# StepperMotorDrivers.net
KiCad netlist of a schematic drawn in Altium Designer
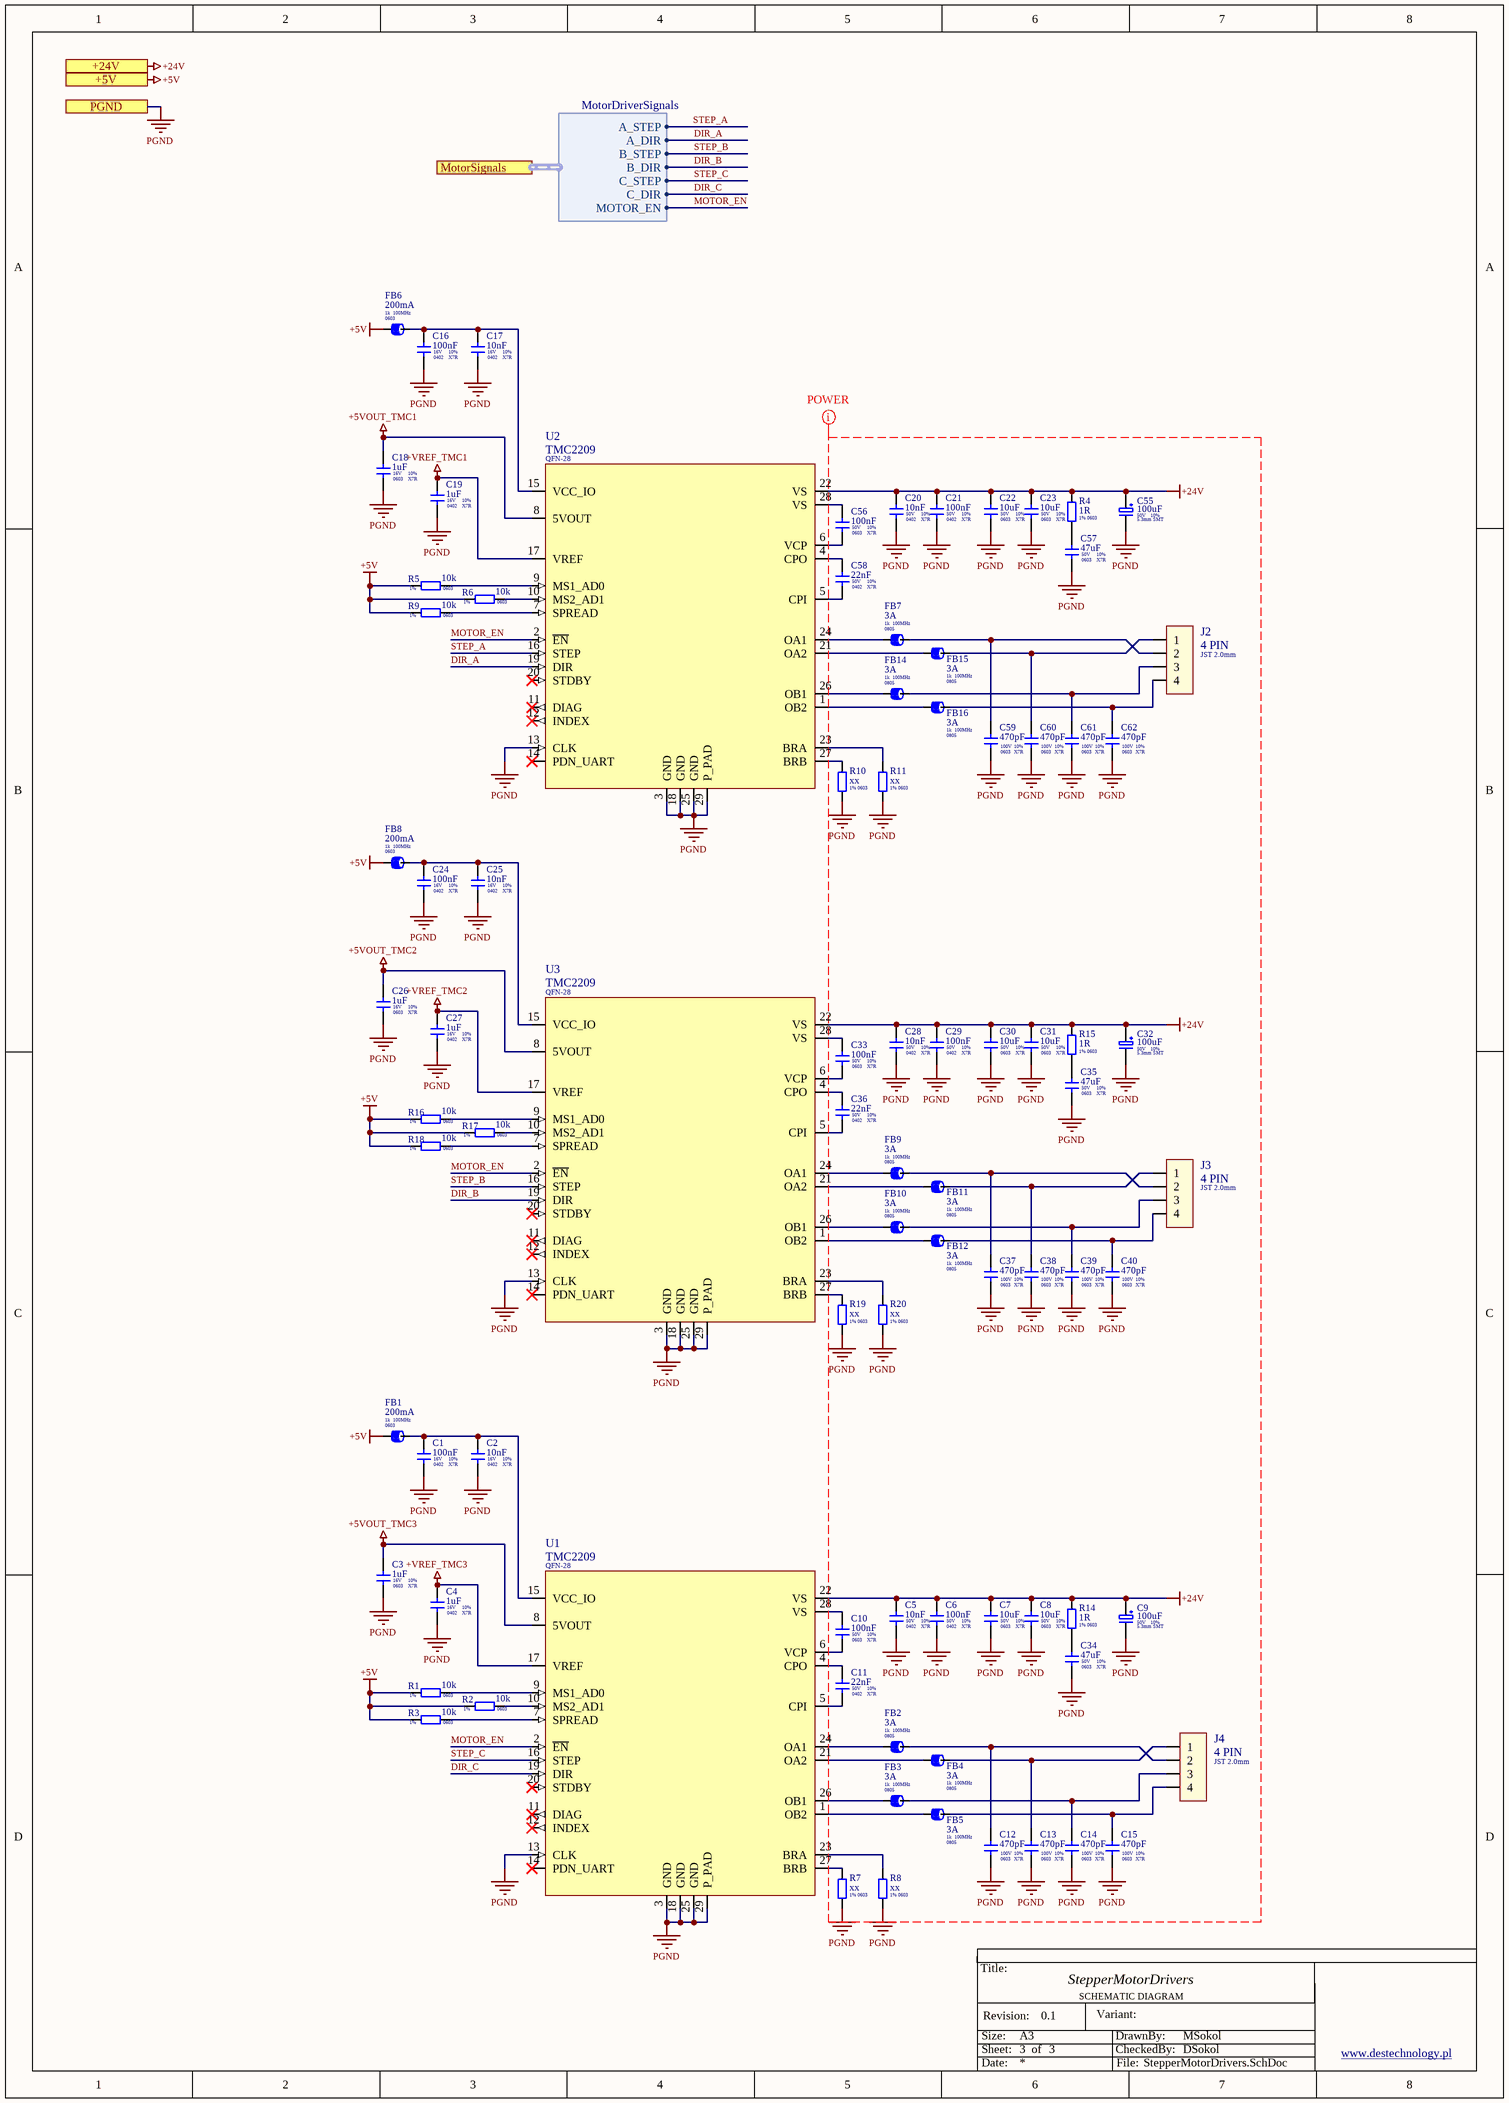
[diagram p0: StepperMotorDrivers.SchDoc]

(export (version "E")
  (design (tool "Eeschema 10.0.6"))
  (components
    (comp (ref "C1")
      (value "100nF")
      (footprint "CAPC1005X04N")
      (fields
        (field (name "DIELECTRICTYPE") "X7R")
        (field (name "VOLTAGE") "16V")
        (field (name "TOLERANT") "10%")
        (field (name "PACKAGE") "0402")
        (field (name "Comment") "100nF/16V")
      )
      (libsource (lib "unnamed") (part "C"))
    )
    (comp (ref "C2")
      (value "10nF")
      (footprint "CAPC1005X04N")
      (fields
        (field (name "DIELECTRICTYPE") "X7R")
        (field (name "VOLTAGE") "16V")
        (field (name "TOLERANT") "10%")
        (field (name "PACKAGE") "0402")
        (field (name "Comment") "10nF/16V")
      )
      (libsource (lib "unnamed") (part "C"))
    )
    (comp (ref "C3")
      (value "1uF")
      (footprint "CAPC1608X06N")
      (fields
        (field (name "DIELECTRICTYPE") "X7R")
        (field (name "VOLTAGE") "16V")
        (field (name "TOLERANT") "10%")
        (field (name "PACKAGE") "0603")
        (field (name "Comment") "1uF/16V")
      )
      (libsource (lib "unnamed") (part "C"))
    )
    (comp (ref "C4")
      (value "1uF")
      (footprint "CAPC1005X04N")
      (fields
        (field (name "DIELECTRICTYPE") "X7R")
        (field (name "VOLTAGE") "16V")
        (field (name "TOLERANT") "10%")
        (field (name "PACKAGE") "0402")
        (field (name "Comment") "1uF/16V")
      )
      (libsource (lib "unnamed") (part "C"))
    )
    (comp (ref "C5")
      (value "10nF")
      (footprint "CAPC1005X04N")
      (fields
        (field (name "DIELECTRICTYPE") "X7R")
        (field (name "VOLTAGE") "50V")
        (field (name "TOLERANT") "10%")
        (field (name "PACKAGE") "0402")
        (field (name "Comment") "10nF/50V")
      )
      (libsource (lib "unnamed") (part "C"))
    )
    (comp (ref "C6")
      (value "100nF")
      (footprint "CAPC1005X04N")
      (fields
        (field (name "DIELECTRICTYPE") "X7R")
        (field (name "VOLTAGE") "50V")
        (field (name "TOLERANT") "10%")
        (field (name "PACKAGE") "0402")
        (field (name "Comment") "100nF/50V")
      )
      (libsource (lib "unnamed") (part "C"))
    )
    (comp (ref "C7")
      (value "10uF")
      (footprint "CAPC1608X06M")
      (fields
        (field (name "DIELECTRICTYPE") "X7R")
        (field (name "VOLTAGE") "50V")
        (field (name "TOLERANT") "10%")
        (field (name "PACKAGE") "0603")
        (field (name "Comment") "10uF/50V")
      )
      (libsource (lib "unnamed") (part "C"))
    )
    (comp (ref "C8")
      (value "10uF")
      (footprint "CAPC1608X06M")
      (fields
        (field (name "DIELECTRICTYPE") "X7R")
        (field (name "VOLTAGE") "50V")
        (field (name "TOLERANT") "10%")
        (field (name "PACKAGE") "0603")
        (field (name "Comment") "10uF/50V")
      )
      (libsource (lib "unnamed") (part "C"))
    )
    (comp (ref "C9")
      (value "100uF")
      (footprint "CAPAE4543X55L")
      (fields
        (field (name "VOLTAGE") "50V")
        (field (name "TOLERANT") "10%")
        (field (name "PACKAGE") "5.3mm SMT")
        (field (name "Comment") "100uF/50V")
      )
      (libsource (lib "unnamed") (part "C_EL"))
    )
    (comp (ref "C10")
      (value "100nF")
      (footprint "CAPC1608X06N")
      (fields
        (field (name "DIELECTRICTYPE") "X7R")
        (field (name "VOLTAGE") "50V")
        (field (name "TOLERANT") "10%")
        (field (name "PACKAGE") "0603")
        (field (name "Comment") "100nF/50V")
      )
      (libsource (lib "unnamed") (part "C"))
    )
    (comp (ref "C11")
      (value "22nF")
      (footprint "CAPC1005X04N")
      (fields
        (field (name "DIELECTRICTYPE") "X7R")
        (field (name "VOLTAGE") "50V")
        (field (name "TOLERANT") "10%")
        (field (name "PACKAGE") "0402")
        (field (name "Comment") "22nF/50V")
      )
      (libsource (lib "unnamed") (part "C"))
    )
    (comp (ref "C12")
      (value "470pF")
      (footprint "CAPC1608X06L")
      (fields
        (field (name "DIELECTRICTYPE") "X7R")
        (field (name "VOLTAGE") "100V")
        (field (name "TOLERANT") "10%")
        (field (name "PACKAGE") "0603")
        (field (name "Comment") "470pF/100V")
      )
      (libsource (lib "unnamed") (part "C"))
    )
    (comp (ref "C13")
      (value "470pF")
      (footprint "CAPC1608X06L")
      (fields
        (field (name "DIELECTRICTYPE") "X7R")
        (field (name "VOLTAGE") "100V")
        (field (name "TOLERANT") "10%")
        (field (name "PACKAGE") "0603")
        (field (name "Comment") "470pF/100V")
      )
      (libsource (lib "unnamed") (part "C"))
    )
    (comp (ref "C14")
      (value "470pF")
      (footprint "CAPC1608X06L")
      (fields
        (field (name "DIELECTRICTYPE") "X7R")
        (field (name "VOLTAGE") "100V")
        (field (name "TOLERANT") "10%")
        (field (name "PACKAGE") "0603")
        (field (name "Comment") "470pF/100V")
      )
      (libsource (lib "unnamed") (part "C"))
    )
    (comp (ref "C15")
      (value "470pF")
      (footprint "CAPC1608X06L")
      (fields
        (field (name "DIELECTRICTYPE") "X7R")
        (field (name "VOLTAGE") "100V")
        (field (name "TOLERANT") "10%")
        (field (name "PACKAGE") "0603")
        (field (name "Comment") "470pF/100V")
      )
      (libsource (lib "unnamed") (part "C"))
    )
    (comp (ref "C16")
      (value "100nF")
      (footprint "CAPC1005X04N")
      (fields
        (field (name "DIELECTRICTYPE") "X7R")
        (field (name "VOLTAGE") "16V")
        (field (name "TOLERANT") "10%")
        (field (name "PACKAGE") "0402")
        (field (name "Comment") "100nF/16V")
      )
      (libsource (lib "unnamed") (part "C"))
    )
    (comp (ref "C17")
      (value "10nF")
      (footprint "CAPC1005X04N")
      (fields
        (field (name "DIELECTRICTYPE") "X7R")
        (field (name "VOLTAGE") "16V")
        (field (name "TOLERANT") "10%")
        (field (name "PACKAGE") "0402")
        (field (name "Comment") "10nF/16V")
      )
      (libsource (lib "unnamed") (part "C"))
    )
    (comp (ref "C18")
      (value "1uF")
      (footprint "CAPC1608X06N")
      (fields
        (field (name "DIELECTRICTYPE") "X7R")
        (field (name "VOLTAGE") "16V")
        (field (name "TOLERANT") "10%")
        (field (name "PACKAGE") "0603")
        (field (name "Comment") "1uF/16V")
      )
      (libsource (lib "unnamed") (part "C"))
    )
    (comp (ref "C19")
      (value "1uF")
      (footprint "CAPC1005X04N")
      (fields
        (field (name "DIELECTRICTYPE") "X7R")
        (field (name "VOLTAGE") "16V")
        (field (name "TOLERANT") "10%")
        (field (name "PACKAGE") "0402")
        (field (name "Comment") "1uF/16V")
      )
      (libsource (lib "unnamed") (part "C"))
    )
    (comp (ref "C20")
      (value "10nF")
      (footprint "CAPC1005X04N")
      (fields
        (field (name "DIELECTRICTYPE") "X7R")
        (field (name "VOLTAGE") "50V")
        (field (name "TOLERANT") "10%")
        (field (name "PACKAGE") "0402")
        (field (name "Comment") "10nF/50V")
      )
      (libsource (lib "unnamed") (part "C"))
    )
    (comp (ref "C21")
      (value "100nF")
      (footprint "CAPC1005X04N")
      (fields
        (field (name "DIELECTRICTYPE") "X7R")
        (field (name "VOLTAGE") "50V")
        (field (name "TOLERANT") "10%")
        (field (name "PACKAGE") "0402")
        (field (name "Comment") "100nF/50V")
      )
      (libsource (lib "unnamed") (part "C"))
    )
    (comp (ref "C22")
      (value "10uF")
      (footprint "CAPC1608X06M")
      (fields
        (field (name "DIELECTRICTYPE") "X7R")
        (field (name "VOLTAGE") "50V")
        (field (name "TOLERANT") "10%")
        (field (name "PACKAGE") "0603")
        (field (name "Comment") "10uF/50V")
      )
      (libsource (lib "unnamed") (part "C"))
    )
    (comp (ref "C23")
      (value "10uF")
      (footprint "CAPC1608X06M")
      (fields
        (field (name "DIELECTRICTYPE") "X7R")
        (field (name "VOLTAGE") "50V")
        (field (name "TOLERANT") "10%")
        (field (name "PACKAGE") "0603")
        (field (name "Comment") "10uF/50V")
      )
      (libsource (lib "unnamed") (part "C"))
    )
    (comp (ref "C24")
      (value "100nF")
      (footprint "CAPC1005X04N")
      (fields
        (field (name "DIELECTRICTYPE") "X7R")
        (field (name "VOLTAGE") "16V")
        (field (name "TOLERANT") "10%")
        (field (name "PACKAGE") "0402")
        (field (name "Comment") "100nF/16V")
      )
      (libsource (lib "unnamed") (part "C"))
    )
    (comp (ref "C25")
      (value "10nF")
      (footprint "CAPC1005X04N")
      (fields
        (field (name "DIELECTRICTYPE") "X7R")
        (field (name "VOLTAGE") "16V")
        (field (name "TOLERANT") "10%")
        (field (name "PACKAGE") "0402")
        (field (name "Comment") "10nF/16V")
      )
      (libsource (lib "unnamed") (part "C"))
    )
    (comp (ref "C26")
      (value "1uF")
      (footprint "CAPC1608X06N")
      (fields
        (field (name "DIELECTRICTYPE") "X7R")
        (field (name "VOLTAGE") "16V")
        (field (name "TOLERANT") "10%")
        (field (name "PACKAGE") "0603")
        (field (name "Comment") "1uF/16V")
      )
      (libsource (lib "unnamed") (part "C"))
    )
    (comp (ref "C27")
      (value "1uF")
      (footprint "CAPC1005X04N")
      (fields
        (field (name "DIELECTRICTYPE") "X7R")
        (field (name "VOLTAGE") "16V")
        (field (name "TOLERANT") "10%")
        (field (name "PACKAGE") "0402")
        (field (name "Comment") "1uF/16V")
      )
      (libsource (lib "unnamed") (part "C"))
    )
    (comp (ref "C28")
      (value "10nF")
      (footprint "CAPC1005X04N")
      (fields
        (field (name "DIELECTRICTYPE") "X7R")
        (field (name "VOLTAGE") "50V")
        (field (name "TOLERANT") "10%")
        (field (name "PACKAGE") "0402")
        (field (name "Comment") "10nF/50V")
      )
      (libsource (lib "unnamed") (part "C"))
    )
    (comp (ref "C29")
      (value "100nF")
      (footprint "CAPC1005X04N")
      (fields
        (field (name "DIELECTRICTYPE") "X7R")
        (field (name "VOLTAGE") "50V")
        (field (name "TOLERANT") "10%")
        (field (name "PACKAGE") "0402")
        (field (name "Comment") "100nF/50V")
      )
      (libsource (lib "unnamed") (part "C"))
    )
    (comp (ref "C30")
      (value "10uF")
      (footprint "CAPC1608X06M")
      (fields
        (field (name "DIELECTRICTYPE") "X7R")
        (field (name "VOLTAGE") "50V")
        (field (name "TOLERANT") "10%")
        (field (name "PACKAGE") "0603")
        (field (name "Comment") "10uF/50V")
      )
      (libsource (lib "unnamed") (part "C"))
    )
    (comp (ref "C31")
      (value "10uF")
      (footprint "CAPC1608X06M")
      (fields
        (field (name "DIELECTRICTYPE") "X7R")
        (field (name "VOLTAGE") "50V")
        (field (name "TOLERANT") "10%")
        (field (name "PACKAGE") "0603")
        (field (name "Comment") "10uF/50V")
      )
      (libsource (lib "unnamed") (part "C"))
    )
    (comp (ref "C32")
      (value "100uF")
      (footprint "CAPAE4543X55L")
      (fields
        (field (name "VOLTAGE") "50V")
        (field (name "TOLERANT") "10%")
        (field (name "PACKAGE") "5.3mm SMT")
        (field (name "Comment") "100uF/50V")
      )
      (libsource (lib "unnamed") (part "C_EL"))
    )
    (comp (ref "C33")
      (value "100nF")
      (footprint "CAPC1608X06N")
      (fields
        (field (name "DIELECTRICTYPE") "X7R")
        (field (name "VOLTAGE") "50V")
        (field (name "TOLERANT") "10%")
        (field (name "PACKAGE") "0603")
        (field (name "Comment") "100nF/50V")
      )
      (libsource (lib "unnamed") (part "C"))
    )
    (comp (ref "C34")
      (value "47uF")
      (footprint "CAPC1608X06M")
      (fields
        (field (name "DIELECTRICTYPE") "X7R")
        (field (name "VOLTAGE") "50V")
        (field (name "TOLERANT") "10%")
        (field (name "PACKAGE") "0603")
        (field (name "Comment") "47uF/50V")
      )
      (libsource (lib "unnamed") (part "C"))
    )
    (comp (ref "C35")
      (value "47uF")
      (footprint "CAPC1608X06M")
      (fields
        (field (name "DIELECTRICTYPE") "X7R")
        (field (name "VOLTAGE") "50V")
        (field (name "TOLERANT") "10%")
        (field (name "PACKAGE") "0603")
        (field (name "Comment") "47uF/50V")
      )
      (libsource (lib "unnamed") (part "C"))
    )
    (comp (ref "C36")
      (value "22nF")
      (footprint "CAPC1005X04N")
      (fields
        (field (name "DIELECTRICTYPE") "X7R")
        (field (name "VOLTAGE") "50V")
        (field (name "TOLERANT") "10%")
        (field (name "PACKAGE") "0402")
        (field (name "Comment") "22nF/50V")
      )
      (libsource (lib "unnamed") (part "C"))
    )
    (comp (ref "C37")
      (value "470pF")
      (footprint "CAPC1608X06L")
      (fields
        (field (name "DIELECTRICTYPE") "X7R")
        (field (name "VOLTAGE") "100V")
        (field (name "TOLERANT") "10%")
        (field (name "PACKAGE") "0603")
        (field (name "Comment") "470pF/100V")
      )
      (libsource (lib "unnamed") (part "C"))
    )
    (comp (ref "C38")
      (value "470pF")
      (footprint "CAPC1608X06L")
      (fields
        (field (name "DIELECTRICTYPE") "X7R")
        (field (name "VOLTAGE") "100V")
        (field (name "TOLERANT") "10%")
        (field (name "PACKAGE") "0603")
        (field (name "Comment") "470pF/100V")
      )
      (libsource (lib "unnamed") (part "C"))
    )
    (comp (ref "C39")
      (value "470pF")
      (footprint "CAPC1608X06L")
      (fields
        (field (name "DIELECTRICTYPE") "X7R")
        (field (name "VOLTAGE") "100V")
        (field (name "TOLERANT") "10%")
        (field (name "PACKAGE") "0603")
        (field (name "Comment") "470pF/100V")
      )
      (libsource (lib "unnamed") (part "C"))
    )
    (comp (ref "C40")
      (value "470pF")
      (footprint "CAPC1608X06L")
      (fields
        (field (name "DIELECTRICTYPE") "X7R")
        (field (name "VOLTAGE") "100V")
        (field (name "TOLERANT") "10%")
        (field (name "PACKAGE") "0603")
        (field (name "Comment") "470pF/100V")
      )
      (libsource (lib "unnamed") (part "C"))
    )
    (comp (ref "C55")
      (value "100uF")
      (footprint "CAPAE4543X55L")
      (fields
        (field (name "VOLTAGE") "50V")
        (field (name "TOLERANT") "10%")
        (field (name "PACKAGE") "5.3mm SMT")
        (field (name "Comment") "100uF/50V")
      )
      (libsource (lib "unnamed") (part "C_EL"))
    )
    (comp (ref "C56")
      (value "100nF")
      (footprint "CAPC1608X06N")
      (fields
        (field (name "DIELECTRICTYPE") "X7R")
        (field (name "VOLTAGE") "50V")
        (field (name "TOLERANT") "10%")
        (field (name "PACKAGE") "0603")
        (field (name "Comment") "100nF/50V")
      )
      (libsource (lib "unnamed") (part "C"))
    )
    (comp (ref "C57")
      (value "47uF")
      (footprint "CAPC1608X06M")
      (fields
        (field (name "DIELECTRICTYPE") "X7R")
        (field (name "VOLTAGE") "50V")
        (field (name "TOLERANT") "10%")
        (field (name "PACKAGE") "0603")
        (field (name "Comment") "47uF/50V")
      )
      (libsource (lib "unnamed") (part "C"))
    )
    (comp (ref "C58")
      (value "22nF")
      (footprint "CAPC1005X04N")
      (fields
        (field (name "DIELECTRICTYPE") "X7R")
        (field (name "VOLTAGE") "50V")
        (field (name "TOLERANT") "10%")
        (field (name "PACKAGE") "0402")
        (field (name "Comment") "22nF/50V")
      )
      (libsource (lib "unnamed") (part "C"))
    )
    (comp (ref "C59")
      (value "470pF")
      (footprint "CAPC1608X06L")
      (fields
        (field (name "DIELECTRICTYPE") "X7R")
        (field (name "VOLTAGE") "100V")
        (field (name "TOLERANT") "10%")
        (field (name "PACKAGE") "0603")
        (field (name "Comment") "470pF/100V")
      )
      (libsource (lib "unnamed") (part "C"))
    )
    (comp (ref "C60")
      (value "470pF")
      (footprint "CAPC1608X06L")
      (fields
        (field (name "DIELECTRICTYPE") "X7R")
        (field (name "VOLTAGE") "100V")
        (field (name "TOLERANT") "10%")
        (field (name "PACKAGE") "0603")
        (field (name "Comment") "470pF/100V")
      )
      (libsource (lib "unnamed") (part "C"))
    )
    (comp (ref "C61")
      (value "470pF")
      (footprint "CAPC1608X06L")
      (fields
        (field (name "DIELECTRICTYPE") "X7R")
        (field (name "VOLTAGE") "100V")
        (field (name "TOLERANT") "10%")
        (field (name "PACKAGE") "0603")
        (field (name "Comment") "470pF/100V")
      )
      (libsource (lib "unnamed") (part "C"))
    )
    (comp (ref "C62")
      (value "470pF")
      (footprint "CAPC1608X06L")
      (fields
        (field (name "DIELECTRICTYPE") "X7R")
        (field (name "VOLTAGE") "100V")
        (field (name "TOLERANT") "10%")
        (field (name "PACKAGE") "0603")
        (field (name "Comment") "470pF/100V")
      )
      (libsource (lib "unnamed") (part "C"))
    )
    (comp (ref "FB1")
      (value "200mA")
      (footprint "INDC1608X06N")
      (description "Ferrite bead - 2-nd Symbol")
      (fields
        (field (name "MIN FREQUENCY") "100MHz")
        (field (name "IMPEDANCE") "1k")
        (field (name "PACKAGE") "0603")
      )
      (libsource (lib "unnamed") (part "FB_1"))
    )
    (comp (ref "FB2")
      (value "3A")
      (footprint "INDC2012X07N")
      (description "Ferrite bead - 2-nd Symbol")
      (fields
        (field (name "MIN FREQUENCY") "100MHz")
        (field (name "IMPEDANCE") "1k")
        (field (name "PACKAGE") "0805")
      )
      (libsource (lib "unnamed") (part "FB_1"))
    )
    (comp (ref "FB3")
      (value "3A")
      (footprint "INDC2012X07N")
      (description "Ferrite bead - 2-nd Symbol")
      (fields
        (field (name "MIN FREQUENCY") "100MHz")
        (field (name "IMPEDANCE") "1k")
        (field (name "PACKAGE") "0805")
      )
      (libsource (lib "unnamed") (part "FB_1"))
    )
    (comp (ref "FB4")
      (value "3A")
      (footprint "INDC2012X07N")
      (description "Ferrite bead - 2-nd Symbol")
      (fields
        (field (name "MIN FREQUENCY") "100MHz")
        (field (name "IMPEDANCE") "1k")
        (field (name "PACKAGE") "0805")
      )
      (libsource (lib "unnamed") (part "FB_1"))
    )
    (comp (ref "FB5")
      (value "3A")
      (footprint "INDC2012X07N")
      (description "Ferrite bead - 2-nd Symbol")
      (fields
        (field (name "MIN FREQUENCY") "100MHz")
        (field (name "IMPEDANCE") "1k")
        (field (name "PACKAGE") "0805")
      )
      (libsource (lib "unnamed") (part "FB_1"))
    )
    (comp (ref "FB6")
      (value "200mA")
      (footprint "INDC1608X06N")
      (description "Ferrite bead - 2-nd Symbol")
      (fields
        (field (name "MIN FREQUENCY") "100MHz")
        (field (name "IMPEDANCE") "1k")
        (field (name "PACKAGE") "0603")
      )
      (libsource (lib "unnamed") (part "FB_1"))
    )
    (comp (ref "FB7")
      (value "3A")
      (footprint "INDC2012X07N")
      (description "Ferrite bead - 2-nd Symbol")
      (fields
        (field (name "MIN FREQUENCY") "100MHz")
        (field (name "IMPEDANCE") "1k")
        (field (name "PACKAGE") "0805")
      )
      (libsource (lib "unnamed") (part "FB_1"))
    )
    (comp (ref "FB8")
      (value "200mA")
      (footprint "INDC1608X06N")
      (description "Ferrite bead - 2-nd Symbol")
      (fields
        (field (name "MIN FREQUENCY") "100MHz")
        (field (name "IMPEDANCE") "1k")
        (field (name "PACKAGE") "0603")
      )
      (libsource (lib "unnamed") (part "FB_1"))
    )
    (comp (ref "FB9")
      (value "3A")
      (footprint "INDC2012X07N")
      (description "Ferrite bead - 2-nd Symbol")
      (fields
        (field (name "MIN FREQUENCY") "100MHz")
        (field (name "IMPEDANCE") "1k")
        (field (name "PACKAGE") "0805")
      )
      (libsource (lib "unnamed") (part "FB_1"))
    )
    (comp (ref "FB10")
      (value "3A")
      (footprint "INDC2012X07N")
      (description "Ferrite bead - 2-nd Symbol")
      (fields
        (field (name "MIN FREQUENCY") "100MHz")
        (field (name "IMPEDANCE") "1k")
        (field (name "PACKAGE") "0805")
      )
      (libsource (lib "unnamed") (part "FB_1"))
    )
    (comp (ref "FB11")
      (value "3A")
      (footprint "INDC2012X07N")
      (description "Ferrite bead - 2-nd Symbol")
      (fields
        (field (name "MIN FREQUENCY") "100MHz")
        (field (name "IMPEDANCE") "1k")
        (field (name "PACKAGE") "0805")
      )
      (libsource (lib "unnamed") (part "FB_1"))
    )
    (comp (ref "FB12")
      (value "3A")
      (footprint "INDC2012X07N")
      (description "Ferrite bead - 2-nd Symbol")
      (fields
        (field (name "MIN FREQUENCY") "100MHz")
        (field (name "IMPEDANCE") "1k")
        (field (name "PACKAGE") "0805")
      )
      (libsource (lib "unnamed") (part "FB_1"))
    )
    (comp (ref "FB14")
      (value "3A")
      (footprint "INDC2012X07N")
      (description "Ferrite bead - 2-nd Symbol")
      (fields
        (field (name "MIN FREQUENCY") "100MHz")
        (field (name "IMPEDANCE") "1k")
        (field (name "PACKAGE") "0805")
      )
      (libsource (lib "unnamed") (part "FB_1"))
    )
    (comp (ref "FB15")
      (value "3A")
      (footprint "INDC2012X07N")
      (description "Ferrite bead - 2-nd Symbol")
      (fields
        (field (name "MIN FREQUENCY") "100MHz")
        (field (name "IMPEDANCE") "1k")
        (field (name "PACKAGE") "0805")
      )
      (libsource (lib "unnamed") (part "FB_1"))
    )
    (comp (ref "FB16")
      (value "3A")
      (footprint "INDC2012X07N")
      (description "Ferrite bead - 2-nd Symbol")
      (fields
        (field (name "MIN FREQUENCY") "100MHz")
        (field (name "IMPEDANCE") "1k")
        (field (name "PACKAGE") "0805")
      )
      (libsource (lib "unnamed") (part "FB_1"))
    )
    (comp (ref "J2")
      (value "4 PIN")
      (footprint "B4B-PH-K-S")
      (fields (field (name "PACKAGE") "JST 2.0mm"))
      (libsource (lib "unnamed") (part "CON_4PIN"))
    )
    (comp (ref "J3")
      (value "4 PIN")
      (footprint "B4B-PH-K-S")
      (fields (field (name "PACKAGE") "JST 2.0mm"))
      (libsource (lib "unnamed") (part "CON_4PIN"))
    )
    (comp (ref "J4")
      (value "4 PIN")
      (footprint "B4B-PH-K-S")
      (fields (field (name "PACKAGE") "JST 2.0mm"))
      (libsource (lib "unnamed") (part "CON_4PIN"))
    )
    (comp (ref "R1")
      (value "10k")
      (footprint "RESC1608X06N")
      (fields
        (field (name "PACKAGE") "0603")
        (field (name "TOLERANCE") "1%")
        (field (name "Comment") "10k 1%")
      )
      (libsource (lib "unnamed") (part "R"))
    )
    (comp (ref "R2")
      (value "10k")
      (footprint "RESC1608X06N")
      (fields
        (field (name "PACKAGE") "0603")
        (field (name "TOLERANCE") "1%")
        (field (name "Comment") "10k 1%")
      )
      (libsource (lib "unnamed") (part "R"))
    )
    (comp (ref "R3")
      (value "10k")
      (footprint "RESC1608X06N")
      (fields
        (field (name "PACKAGE") "0603")
        (field (name "TOLERANCE") "1%")
        (field (name "Comment") "10k 1%")
      )
      (libsource (lib "unnamed") (part "R"))
    )
    (comp (ref "R4")
      (value "1R")
      (footprint "RESC1608X06N")
      (fields
        (field (name "PACKAGE") "0603")
        (field (name "TOLERANCE") "1%")
        (field (name "Comment") "1R 1%")
      )
      (libsource (lib "") (part "R_1"))
    )
    (comp (ref "R5")
      (value "10k")
      (footprint "RESC1608X06N")
      (fields
        (field (name "PACKAGE") "0603")
        (field (name "TOLERANCE") "1%")
        (field (name "Comment") "10k 1%")
      )
      (libsource (lib "unnamed") (part "R"))
    )
    (comp (ref "R6")
      (value "10k")
      (footprint "RESC1608X06N")
      (fields
        (field (name "PACKAGE") "0603")
        (field (name "TOLERANCE") "1%")
        (field (name "Comment") "10k 1%")
      )
      (libsource (lib "unnamed") (part "R"))
    )
    (comp (ref "R7")
      (value "xx")
      (footprint "RESC1608X06N")
      (fields
        (field (name "PACKAGE") "0603")
        (field (name "TOLERANCE") "1%")
        (field (name "Comment") "xx 1%")
      )
      (libsource (lib "") (part "R_1"))
    )
    (comp (ref "R8")
      (value "xx")
      (footprint "RESC1608X06N")
      (fields
        (field (name "PACKAGE") "0603")
        (field (name "TOLERANCE") "1%")
        (field (name "Comment") "xx 1%")
      )
      (libsource (lib "") (part "R_1"))
    )
    (comp (ref "R9")
      (value "10k")
      (footprint "RESC1608X06N")
      (fields
        (field (name "PACKAGE") "0603")
        (field (name "TOLERANCE") "1%")
        (field (name "Comment") "10k 1%")
      )
      (libsource (lib "unnamed") (part "R"))
    )
    (comp (ref "R10")
      (value "xx")
      (footprint "RESC1608X06N")
      (fields
        (field (name "PACKAGE") "0603")
        (field (name "TOLERANCE") "1%")
        (field (name "Comment") "xx 1%")
      )
      (libsource (lib "") (part "R_1"))
    )
    (comp (ref "R11")
      (value "xx")
      (footprint "RESC1608X06N")
      (fields
        (field (name "PACKAGE") "0603")
        (field (name "TOLERANCE") "1%")
        (field (name "Comment") "xx 1%")
      )
      (libsource (lib "") (part "R_1"))
    )
    (comp (ref "R14")
      (value "1R")
      (footprint "RESC1608X06N")
      (fields
        (field (name "PACKAGE") "0603")
        (field (name "TOLERANCE") "1%")
        (field (name "Comment") "1R 1%")
      )
      (libsource (lib "") (part "R_1"))
    )
    (comp (ref "R15")
      (value "1R")
      (footprint "RESC1608X06N")
      (fields
        (field (name "PACKAGE") "0603")
        (field (name "TOLERANCE") "1%")
        (field (name "Comment") "1R 1%")
      )
      (libsource (lib "") (part "R_1"))
    )
    (comp (ref "R16")
      (value "10k")
      (footprint "RESC1608X06N")
      (fields
        (field (name "PACKAGE") "0603")
        (field (name "TOLERANCE") "1%")
        (field (name "Comment") "10k 1%")
      )
      (libsource (lib "unnamed") (part "R"))
    )
    (comp (ref "R17")
      (value "10k")
      (footprint "RESC1608X06N")
      (fields
        (field (name "PACKAGE") "0603")
        (field (name "TOLERANCE") "1%")
        (field (name "Comment") "10k 1%")
      )
      (libsource (lib "unnamed") (part "R"))
    )
    (comp (ref "R18")
      (value "10k")
      (footprint "RESC1608X06N")
      (fields
        (field (name "PACKAGE") "0603")
        (field (name "TOLERANCE") "1%")
        (field (name "Comment") "10k 1%")
      )
      (libsource (lib "unnamed") (part "R"))
    )
    (comp (ref "R19")
      (value "xx")
      (footprint "RESC1608X06N")
      (fields
        (field (name "PACKAGE") "0603")
        (field (name "TOLERANCE") "1%")
        (field (name "Comment") "xx 1%")
      )
      (libsource (lib "") (part "R_1"))
    )
    (comp (ref "R20")
      (value "xx")
      (footprint "RESC1608X06N")
      (fields
        (field (name "PACKAGE") "0603")
        (field (name "TOLERANCE") "1%")
        (field (name "Comment") "xx 1%")
      )
      (libsource (lib "") (part "R_1"))
    )
    (comp (ref "U1")
      (value "TMC2209")
      (footprint "QFN50P500X500X90_HS-29N")
      (fields (field (name "PACKAGE") "QFN-28"))
      (libsource (lib "unnamed") (part "TMC2209"))
    )
    (comp (ref "U2")
      (value "TMC2209")
      (footprint "QFN50P500X500X90_HS-29N")
      (fields (field (name "PACKAGE") "QFN-28"))
      (libsource (lib "unnamed") (part "TMC2209"))
    )
    (comp (ref "U3")
      (value "TMC2209")
      (footprint "QFN50P500X500X90_HS-29N")
      (fields (field (name "PACKAGE") "QFN-28"))
      (libsource (lib "unnamed") (part "TMC2209"))
    )
  )
  (nets
    (net (code "2") (name "+5V") (class "Default")
      (node (ref "FB1") (pin "1") (pintype "passive"))
      (node (ref "FB6") (pin "1") (pintype "passive"))
      (node (ref "FB8") (pin "1") (pintype "passive"))
      (node (ref "R1") (pin "1") (pinfunction "1_1") (pintype "passive"))
      (node (ref "R16") (pin "1") (pinfunction "1_1") (pintype "passive"))
      (node (ref "R17") (pin "1") (pinfunction "1_1") (pintype "passive"))
      (node (ref "R18") (pin "1") (pinfunction "1_1") (pintype "passive"))
      (node (ref "R2") (pin "1") (pinfunction "1_1") (pintype "passive"))
      (node (ref "R3") (pin "1") (pinfunction "1_1") (pintype "passive"))
      (node (ref "R5") (pin "1") (pinfunction "1_1") (pintype "passive"))
      (node (ref "R6") (pin "1") (pinfunction "1_1") (pintype "passive"))
      (node (ref "R9") (pin "1") (pinfunction "1_1") (pintype "passive"))
    )
    (net (code "3") (name "+5VOUT_TMC1") (class "Default")
      (node (ref "C18") (pin "2") (pinfunction "2_2") (pintype "passive"))
      (node (ref "U2") (pin "8") (pinfunction "5VOUT_8") (pintype "passive"))
    )
    (net (code "4") (name "+5VOUT_TMC2") (class "Default")
      (node (ref "C26") (pin "2") (pinfunction "2_2") (pintype "passive"))
      (node (ref "U3") (pin "8") (pinfunction "5VOUT_8") (pintype "passive"))
    )
    (net (code "5") (name "+5VOUT_TMC3") (class "Default")
      (node (ref "C3") (pin "2") (pinfunction "2_2") (pintype "passive"))
      (node (ref "U1") (pin "8") (pinfunction "5VOUT_8") (pintype "passive"))
    )
    (net (code "6") (name "+24V") (class "Default")
      (node (ref "C20") (pin "2") (pinfunction "2_2") (pintype "passive"))
      (node (ref "C21") (pin "2") (pinfunction "2_2") (pintype "passive"))
      (node (ref "C22") (pin "2") (pinfunction "2_2") (pintype "passive"))
      (node (ref "C23") (pin "2") (pinfunction "2_2") (pintype "passive"))
      (node (ref "C28") (pin "2") (pinfunction "2_2") (pintype "passive"))
      (node (ref "C29") (pin "2") (pinfunction "2_2") (pintype "passive"))
      (node (ref "C30") (pin "2") (pinfunction "2_2") (pintype "passive"))
      (node (ref "C31") (pin "2") (pinfunction "2_2") (pintype "passive"))
      (node (ref "C32") (pin "1") (pinfunction "1_1") (pintype "passive"))
      (node (ref "C5") (pin "2") (pinfunction "2_2") (pintype "passive"))
      (node (ref "C55") (pin "1") (pinfunction "1_1") (pintype "passive"))
      (node (ref "C6") (pin "2") (pinfunction "2_2") (pintype "passive"))
      (node (ref "C7") (pin "2") (pinfunction "2_2") (pintype "passive"))
      (node (ref "C8") (pin "2") (pinfunction "2_2") (pintype "passive"))
      (node (ref "C9") (pin "1") (pinfunction "1_1") (pintype "passive"))
      (node (ref "R14") (pin "1") (pinfunction "1_1") (pintype "passive"))
      (node (ref "R15") (pin "1") (pinfunction "1_1") (pintype "passive"))
      (node (ref "R4") (pin "1") (pinfunction "1_1") (pintype "passive"))
      (node (ref "U1") (pin "22") (pinfunction "VS_22") (pintype "passive"))
      (node (ref "U2") (pin "22") (pinfunction "VS_22") (pintype "passive"))
      (node (ref "U3") (pin "22") (pinfunction "VS_22") (pintype "passive"))
    )
    (net (code "7") (name "+VREF_TMC1") (class "Default")
      (node (ref "C19") (pin "2") (pinfunction "2_2") (pintype "passive"))
      (node (ref "U2") (pin "17") (pinfunction "VREF_17") (pintype "passive"))
    )
    (net (code "8") (name "+VREF_TMC2") (class "Default")
      (node (ref "C27") (pin "2") (pinfunction "2_2") (pintype "passive"))
      (node (ref "U3") (pin "17") (pinfunction "VREF_17") (pintype "passive"))
    )
    (net (code "9") (name "+VREF_TMC3") (class "Default")
      (node (ref "C4") (pin "2") (pinfunction "2_2") (pintype "passive"))
      (node (ref "U1") (pin "17") (pinfunction "VREF_17") (pintype "passive"))
    )
    (net (code "10") (name "/DIR_A") (class "Default")
      (node (ref "U2") (pin "19") (pinfunction "DIR_19") (pintype "input"))
    )
    (net (code "11") (name "/DIR_B") (class "Default")
      (node (ref "U3") (pin "19") (pinfunction "DIR_19") (pintype "input"))
    )
    (net (code "12") (name "/DIR_C") (class "Default")
      (node (ref "U1") (pin "19") (pinfunction "DIR_19") (pintype "input"))
    )
    (net (code "13") (name "/MOTOR_EN") (class "Default")
      (node (ref "U1") (pin "2") (pinfunction "~{EN}_2") (pintype "input"))
      (node (ref "U2") (pin "2") (pinfunction "~{EN}_2") (pintype "input"))
      (node (ref "U3") (pin "2") (pinfunction "~{EN}_2") (pintype "input"))
    )
    (net (code "14") (name "/STEP_A") (class "Default")
      (node (ref "U2") (pin "16") (pinfunction "STEP_16") (pintype "input"))
    )
    (net (code "15") (name "/STEP_B") (class "Default")
      (node (ref "U3") (pin "16") (pinfunction "STEP_16") (pintype "input"))
    )
    (net (code "16") (name "/STEP_C") (class "Default")
      (node (ref "U1") (pin "16") (pinfunction "STEP_16") (pintype "input"))
    )
    (net (code "18") (name "Net-(C10-Pad2)") (class "Default")
      (node (ref "C10") (pin "2") (pinfunction "2_2") (pintype "passive"))
      (node (ref "U1") (pin "28") (pinfunction "VS_28") (pintype "passive"))
    )
    (net (code "19") (name "Net-(C12-Pad2)") (class "Default")
      (node (ref "C12") (pin "2") (pinfunction "2_2") (pintype "passive"))
      (node (ref "FB2") (pin "2") (pintype "passive"))
      (node (ref "J4") (pin "2") (pinfunction "2_2") (pintype "passive"))
    )
    (net (code "20") (name "Net-(C13-Pad2)") (class "Default")
      (node (ref "C13") (pin "2") (pinfunction "2_2") (pintype "passive"))
      (node (ref "FB4") (pin "2") (pintype "passive"))
      (node (ref "J4") (pin "1") (pinfunction "1_1") (pintype "passive"))
    )
    (net (code "21") (name "Net-(C14-Pad2)") (class "Default")
      (node (ref "C14") (pin "2") (pinfunction "2_2") (pintype "passive"))
      (node (ref "FB3") (pin "2") (pintype "passive"))
      (node (ref "J4") (pin "3") (pinfunction "3_3") (pintype "passive"))
    )
    (net (code "22") (name "Net-(C15-Pad2)") (class "Default")
      (node (ref "C15") (pin "2") (pinfunction "2_2") (pintype "passive"))
      (node (ref "FB5") (pin "2") (pintype "passive"))
      (node (ref "J4") (pin "4") (pinfunction "4_4") (pintype "passive"))
    )
    (net (code "23") (name "Net-(C33-Pad2)") (class "Default")
      (node (ref "C33") (pin "2") (pinfunction "2_2") (pintype "passive"))
      (node (ref "U3") (pin "28") (pinfunction "VS_28") (pintype "passive"))
    )
    (net (code "24") (name "Net-(C34-Pad2)") (class "Default")
      (node (ref "C34") (pin "2") (pinfunction "2_2") (pintype "passive"))
      (node (ref "R14") (pin "2") (pinfunction "2_2") (pintype "passive"))
    )
    (net (code "25") (name "Net-(C35-Pad2)") (class "Default")
      (node (ref "C35") (pin "2") (pinfunction "2_2") (pintype "passive"))
      (node (ref "R15") (pin "2") (pinfunction "2_2") (pintype "passive"))
    )
    (net (code "26") (name "Net-(C37-Pad2)") (class "Default")
      (node (ref "C37") (pin "2") (pinfunction "2_2") (pintype "passive"))
      (node (ref "FB9") (pin "2") (pintype "passive"))
      (node (ref "J3") (pin "2") (pinfunction "2_2") (pintype "passive"))
    )
    (net (code "27") (name "Net-(C38-Pad2)") (class "Default")
      (node (ref "C38") (pin "2") (pinfunction "2_2") (pintype "passive"))
      (node (ref "FB11") (pin "2") (pintype "passive"))
      (node (ref "J3") (pin "1") (pinfunction "1_1") (pintype "passive"))
    )
    (net (code "28") (name "Net-(C39-Pad2)") (class "Default")
      (node (ref "C39") (pin "2") (pinfunction "2_2") (pintype "passive"))
      (node (ref "FB10") (pin "2") (pintype "passive"))
      (node (ref "J3") (pin "3") (pinfunction "3_3") (pintype "passive"))
    )
    (net (code "29") (name "Net-(C40-Pad2)") (class "Default")
      (node (ref "C40") (pin "2") (pinfunction "2_2") (pintype "passive"))
      (node (ref "FB12") (pin "2") (pintype "passive"))
      (node (ref "J3") (pin "4") (pinfunction "4_4") (pintype "passive"))
    )
    (net (code "30") (name "Net-(C56-Pad2)") (class "Default")
      (node (ref "C56") (pin "2") (pinfunction "2_2") (pintype "passive"))
      (node (ref "U2") (pin "28") (pinfunction "VS_28") (pintype "passive"))
    )
    (net (code "31") (name "Net-(C57-Pad2)") (class "Default")
      (node (ref "C57") (pin "2") (pinfunction "2_2") (pintype "passive"))
      (node (ref "R4") (pin "2") (pinfunction "2_2") (pintype "passive"))
    )
    (net (code "32") (name "Net-(C59-Pad2)") (class "Default")
      (node (ref "C59") (pin "2") (pinfunction "2_2") (pintype "passive"))
      (node (ref "FB7") (pin "2") (pintype "passive"))
      (node (ref "J2") (pin "2") (pinfunction "2_2") (pintype "passive"))
    )
    (net (code "33") (name "Net-(C60-Pad2)") (class "Default")
      (node (ref "C60") (pin "2") (pinfunction "2_2") (pintype "passive"))
      (node (ref "FB15") (pin "2") (pintype "passive"))
      (node (ref "J2") (pin "1") (pinfunction "1_1") (pintype "passive"))
    )
    (net (code "34") (name "Net-(C61-Pad2)") (class "Default")
      (node (ref "C61") (pin "2") (pinfunction "2_2") (pintype "passive"))
      (node (ref "FB14") (pin "2") (pintype "passive"))
      (node (ref "J2") (pin "3") (pinfunction "3_3") (pintype "passive"))
    )
    (net (code "35") (name "Net-(C62-Pad2)") (class "Default")
      (node (ref "C62") (pin "2") (pinfunction "2_2") (pintype "passive"))
      (node (ref "FB16") (pin "2") (pintype "passive"))
      (node (ref "J2") (pin "4") (pinfunction "4_4") (pintype "passive"))
    )
    (net (code "36") (name "Net-(U1-BRA)") (class "Default")
      (node (ref "R8") (pin "1") (pinfunction "1_1") (pintype "passive"))
      (node (ref "U1") (pin "23") (pinfunction "BRA_23") (pintype "passive"))
    )
    (net (code "37") (name "Net-(U1-BRB)") (class "Default")
      (node (ref "R7") (pin "1") (pinfunction "1_1") (pintype "passive"))
      (node (ref "U1") (pin "27") (pinfunction "BRB_27") (pintype "passive"))
    )
    (net (code "38") (name "Net-(U1-CPI)") (class "Default")
      (node (ref "C11") (pin "1") (pinfunction "1_1") (pintype "passive"))
      (node (ref "U1") (pin "5") (pinfunction "CPI_5") (pintype "passive"))
    )
    (net (code "39") (name "Net-(U1-CPO)") (class "Default")
      (node (ref "C11") (pin "2") (pinfunction "2_2") (pintype "passive"))
      (node (ref "U1") (pin "4") (pinfunction "CPO_4") (pintype "passive"))
    )
    (net (code "40") (name "Net-(U1-MS1_AD0)") (class "Default")
      (node (ref "R1") (pin "2") (pinfunction "2_2") (pintype "passive"))
      (node (ref "U1") (pin "9") (pinfunction "MS1_AD0_9") (pintype "input"))
    )
    (net (code "41") (name "Net-(U1-MS2_AD1)") (class "Default")
      (node (ref "R2") (pin "2") (pinfunction "2_2") (pintype "passive"))
      (node (ref "U1") (pin "10") (pinfunction "MS2_AD1_10") (pintype "input"))
    )
    (net (code "42") (name "Net-(U1-OA1)") (class "Default")
      (node (ref "FB2") (pin "1") (pintype "passive"))
      (node (ref "U1") (pin "24") (pinfunction "OA1_24") (pintype "passive"))
    )
    (net (code "43") (name "Net-(U1-OA2)") (class "Default")
      (node (ref "FB4") (pin "1") (pintype "passive"))
      (node (ref "U1") (pin "21") (pinfunction "OA2_21") (pintype "passive"))
    )
    (net (code "44") (name "Net-(U1-OB1)") (class "Default")
      (node (ref "FB3") (pin "1") (pintype "passive"))
      (node (ref "U1") (pin "26") (pinfunction "OB1_26") (pintype "passive"))
    )
    (net (code "45") (name "Net-(U1-OB2)") (class "Default")
      (node (ref "FB5") (pin "1") (pintype "passive"))
      (node (ref "U1") (pin "1") (pinfunction "OB2_1") (pintype "passive"))
    )
    (net (code "46") (name "Net-(U1-SPREAD)") (class "Default")
      (node (ref "R3") (pin "2") (pinfunction "2_2") (pintype "passive"))
      (node (ref "U1") (pin "7") (pinfunction "SPREAD_7") (pintype "input"))
    )
    (net (code "47") (name "Net-(U1-VCC_IO)") (class "Default")
      (node (ref "C1") (pin "2") (pinfunction "2_2") (pintype "passive"))
      (node (ref "C2") (pin "2") (pinfunction "2_2") (pintype "passive"))
      (node (ref "FB1") (pin "2") (pintype "passive"))
      (node (ref "U1") (pin "15") (pinfunction "VCC_IO_15") (pintype "passive"))
    )
    (net (code "48") (name "Net-(U1-VCP)") (class "Default")
      (node (ref "C10") (pin "1") (pinfunction "1_1") (pintype "passive"))
      (node (ref "U1") (pin "6") (pinfunction "VCP_6") (pintype "passive"))
    )
    (net (code "49") (name "Net-(U2-BRA)") (class "Default")
      (node (ref "R11") (pin "1") (pinfunction "1_1") (pintype "passive"))
      (node (ref "U2") (pin "23") (pinfunction "BRA_23") (pintype "passive"))
    )
    (net (code "50") (name "Net-(U2-BRB)") (class "Default")
      (node (ref "R10") (pin "1") (pinfunction "1_1") (pintype "passive"))
      (node (ref "U2") (pin "27") (pinfunction "BRB_27") (pintype "passive"))
    )
    (net (code "51") (name "Net-(U2-CPI)") (class "Default")
      (node (ref "C58") (pin "1") (pinfunction "1_1") (pintype "passive"))
      (node (ref "U2") (pin "5") (pinfunction "CPI_5") (pintype "passive"))
    )
    (net (code "52") (name "Net-(U2-CPO)") (class "Default")
      (node (ref "C58") (pin "2") (pinfunction "2_2") (pintype "passive"))
      (node (ref "U2") (pin "4") (pinfunction "CPO_4") (pintype "passive"))
    )
    (net (code "53") (name "Net-(U2-MS1_AD0)") (class "Default")
      (node (ref "R5") (pin "2") (pinfunction "2_2") (pintype "passive"))
      (node (ref "U2") (pin "9") (pinfunction "MS1_AD0_9") (pintype "input"))
    )
    (net (code "54") (name "Net-(U2-MS2_AD1)") (class "Default")
      (node (ref "R6") (pin "2") (pinfunction "2_2") (pintype "passive"))
      (node (ref "U2") (pin "10") (pinfunction "MS2_AD1_10") (pintype "input"))
    )
    (net (code "55") (name "Net-(U2-OA1)") (class "Default")
      (node (ref "FB7") (pin "1") (pintype "passive"))
      (node (ref "U2") (pin "24") (pinfunction "OA1_24") (pintype "passive"))
    )
    (net (code "56") (name "Net-(U2-OA2)") (class "Default")
      (node (ref "FB15") (pin "1") (pintype "passive"))
      (node (ref "U2") (pin "21") (pinfunction "OA2_21") (pintype "passive"))
    )
    (net (code "57") (name "Net-(U2-OB1)") (class "Default")
      (node (ref "FB14") (pin "1") (pintype "passive"))
      (node (ref "U2") (pin "26") (pinfunction "OB1_26") (pintype "passive"))
    )
    (net (code "58") (name "Net-(U2-OB2)") (class "Default")
      (node (ref "FB16") (pin "1") (pintype "passive"))
      (node (ref "U2") (pin "1") (pinfunction "OB2_1") (pintype "passive"))
    )
    (net (code "59") (name "Net-(U2-SPREAD)") (class "Default")
      (node (ref "R9") (pin "2") (pinfunction "2_2") (pintype "passive"))
      (node (ref "U2") (pin "7") (pinfunction "SPREAD_7") (pintype "input"))
    )
    (net (code "60") (name "Net-(U2-VCC_IO)") (class "Default")
      (node (ref "C16") (pin "2") (pinfunction "2_2") (pintype "passive"))
      (node (ref "C17") (pin "2") (pinfunction "2_2") (pintype "passive"))
      (node (ref "FB6") (pin "2") (pintype "passive"))
      (node (ref "U2") (pin "15") (pinfunction "VCC_IO_15") (pintype "passive"))
    )
    (net (code "61") (name "Net-(U2-VCP)") (class "Default")
      (node (ref "C56") (pin "1") (pinfunction "1_1") (pintype "passive"))
      (node (ref "U2") (pin "6") (pinfunction "VCP_6") (pintype "passive"))
    )
    (net (code "62") (name "Net-(U3-BRA)") (class "Default")
      (node (ref "R20") (pin "1") (pinfunction "1_1") (pintype "passive"))
      (node (ref "U3") (pin "23") (pinfunction "BRA_23") (pintype "passive"))
    )
    (net (code "63") (name "Net-(U3-BRB)") (class "Default")
      (node (ref "R19") (pin "1") (pinfunction "1_1") (pintype "passive"))
      (node (ref "U3") (pin "27") (pinfunction "BRB_27") (pintype "passive"))
    )
    (net (code "64") (name "Net-(U3-CPI)") (class "Default")
      (node (ref "C36") (pin "1") (pinfunction "1_1") (pintype "passive"))
      (node (ref "U3") (pin "5") (pinfunction "CPI_5") (pintype "passive"))
    )
    (net (code "65") (name "Net-(U3-CPO)") (class "Default")
      (node (ref "C36") (pin "2") (pinfunction "2_2") (pintype "passive"))
      (node (ref "U3") (pin "4") (pinfunction "CPO_4") (pintype "passive"))
    )
    (net (code "66") (name "Net-(U3-MS1_AD0)") (class "Default")
      (node (ref "R16") (pin "2") (pinfunction "2_2") (pintype "passive"))
      (node (ref "U3") (pin "9") (pinfunction "MS1_AD0_9") (pintype "input"))
    )
    (net (code "67") (name "Net-(U3-MS2_AD1)") (class "Default")
      (node (ref "R17") (pin "2") (pinfunction "2_2") (pintype "passive"))
      (node (ref "U3") (pin "10") (pinfunction "MS2_AD1_10") (pintype "input"))
    )
    (net (code "68") (name "Net-(U3-OA1)") (class "Default")
      (node (ref "FB9") (pin "1") (pintype "passive"))
      (node (ref "U3") (pin "24") (pinfunction "OA1_24") (pintype "passive"))
    )
    (net (code "69") (name "Net-(U3-OA2)") (class "Default")
      (node (ref "FB11") (pin "1") (pintype "passive"))
      (node (ref "U3") (pin "21") (pinfunction "OA2_21") (pintype "passive"))
    )
    (net (code "70") (name "Net-(U3-OB1)") (class "Default")
      (node (ref "FB10") (pin "1") (pintype "passive"))
      (node (ref "U3") (pin "26") (pinfunction "OB1_26") (pintype "passive"))
    )
    (net (code "71") (name "Net-(U3-OB2)") (class "Default")
      (node (ref "FB12") (pin "1") (pintype "passive"))
      (node (ref "U3") (pin "1") (pinfunction "OB2_1") (pintype "passive"))
    )
    (net (code "72") (name "Net-(U3-SPREAD)") (class "Default")
      (node (ref "R18") (pin "2") (pinfunction "2_2") (pintype "passive"))
      (node (ref "U3") (pin "7") (pinfunction "SPREAD_7") (pintype "input"))
    )
    (net (code "73") (name "Net-(U3-VCC_IO)") (class "Default")
      (node (ref "C24") (pin "2") (pinfunction "2_2") (pintype "passive"))
      (node (ref "C25") (pin "2") (pinfunction "2_2") (pintype "passive"))
      (node (ref "FB8") (pin "2") (pintype "passive"))
      (node (ref "U3") (pin "15") (pinfunction "VCC_IO_15") (pintype "passive"))
    )
    (net (code "74") (name "Net-(U3-VCP)") (class "Default")
      (node (ref "C33") (pin "1") (pinfunction "1_1") (pintype "passive"))
      (node (ref "U3") (pin "6") (pinfunction "VCP_6") (pintype "passive"))
    )
    (net (code "75") (name "PGND") (class "Default")
      (node (ref "C1") (pin "1") (pinfunction "1_1") (pintype "passive"))
      (node (ref "C12") (pin "1") (pinfunction "1_1") (pintype "passive"))
      (node (ref "C13") (pin "1") (pinfunction "1_1") (pintype "passive"))
      (node (ref "C14") (pin "1") (pinfunction "1_1") (pintype "passive"))
      (node (ref "C15") (pin "1") (pinfunction "1_1") (pintype "passive"))
      (node (ref "C16") (pin "1") (pinfunction "1_1") (pintype "passive"))
      (node (ref "C17") (pin "1") (pinfunction "1_1") (pintype "passive"))
      (node (ref "C18") (pin "1") (pinfunction "1_1") (pintype "passive"))
      (node (ref "C19") (pin "1") (pinfunction "1_1") (pintype "passive"))
      (node (ref "C2") (pin "1") (pinfunction "1_1") (pintype "passive"))
      (node (ref "C20") (pin "1") (pinfunction "1_1") (pintype "passive"))
      (node (ref "C21") (pin "1") (pinfunction "1_1") (pintype "passive"))
      (node (ref "C22") (pin "1") (pinfunction "1_1") (pintype "passive"))
      (node (ref "C23") (pin "1") (pinfunction "1_1") (pintype "passive"))
      (node (ref "C24") (pin "1") (pinfunction "1_1") (pintype "passive"))
      (node (ref "C25") (pin "1") (pinfunction "1_1") (pintype "passive"))
      (node (ref "C26") (pin "1") (pinfunction "1_1") (pintype "passive"))
      (node (ref "C27") (pin "1") (pinfunction "1_1") (pintype "passive"))
      (node (ref "C28") (pin "1") (pinfunction "1_1") (pintype "passive"))
      (node (ref "C29") (pin "1") (pinfunction "1_1") (pintype "passive"))
      (node (ref "C3") (pin "1") (pinfunction "1_1") (pintype "passive"))
      (node (ref "C30") (pin "1") (pinfunction "1_1") (pintype "passive"))
      (node (ref "C31") (pin "1") (pinfunction "1_1") (pintype "passive"))
      (node (ref "C32") (pin "2") (pinfunction "2_2") (pintype "passive"))
      (node (ref "C34") (pin "1") (pinfunction "1_1") (pintype "passive"))
      (node (ref "C35") (pin "1") (pinfunction "1_1") (pintype "passive"))
      (node (ref "C37") (pin "1") (pinfunction "1_1") (pintype "passive"))
      (node (ref "C38") (pin "1") (pinfunction "1_1") (pintype "passive"))
      (node (ref "C39") (pin "1") (pinfunction "1_1") (pintype "passive"))
      (node (ref "C4") (pin "1") (pinfunction "1_1") (pintype "passive"))
      (node (ref "C40") (pin "1") (pinfunction "1_1") (pintype "passive"))
      (node (ref "C5") (pin "1") (pinfunction "1_1") (pintype "passive"))
      (node (ref "C55") (pin "2") (pinfunction "2_2") (pintype "passive"))
      (node (ref "C57") (pin "1") (pinfunction "1_1") (pintype "passive"))
      (node (ref "C59") (pin "1") (pinfunction "1_1") (pintype "passive"))
      (node (ref "C6") (pin "1") (pinfunction "1_1") (pintype "passive"))
      (node (ref "C60") (pin "1") (pinfunction "1_1") (pintype "passive"))
      (node (ref "C61") (pin "1") (pinfunction "1_1") (pintype "passive"))
      (node (ref "C62") (pin "1") (pinfunction "1_1") (pintype "passive"))
      (node (ref "C7") (pin "1") (pinfunction "1_1") (pintype "passive"))
      (node (ref "C8") (pin "1") (pinfunction "1_1") (pintype "passive"))
      (node (ref "C9") (pin "2") (pinfunction "2_2") (pintype "passive"))
      (node (ref "R10") (pin "2") (pinfunction "2_2") (pintype "passive"))
      (node (ref "R11") (pin "2") (pinfunction "2_2") (pintype "passive"))
      (node (ref "R19") (pin "2") (pinfunction "2_2") (pintype "passive"))
      (node (ref "R20") (pin "2") (pinfunction "2_2") (pintype "passive"))
      (node (ref "R7") (pin "2") (pinfunction "2_2") (pintype "passive"))
      (node (ref "R8") (pin "2") (pinfunction "2_2") (pintype "passive"))
      (node (ref "U1") (pin "13") (pinfunction "CLK_13") (pintype "input"))
      (node (ref "U1") (pin "18") (pinfunction "GND_18") (pintype "passive"))
      (node (ref "U1") (pin "25") (pinfunction "GND_25") (pintype "passive"))
      (node (ref "U1") (pin "29") (pinfunction "P_PAD_29") (pintype "passive"))
      (node (ref "U1") (pin "3") (pinfunction "GND_3") (pintype "passive"))
      (node (ref "U2") (pin "13") (pinfunction "CLK_13") (pintype "input"))
      (node (ref "U2") (pin "18") (pinfunction "GND_18") (pintype "passive"))
      (node (ref "U2") (pin "25") (pinfunction "GND_25") (pintype "passive"))
      (node (ref "U2") (pin "29") (pinfunction "P_PAD_29") (pintype "passive"))
      (node (ref "U2") (pin "3") (pinfunction "GND_3") (pintype "passive"))
      (node (ref "U3") (pin "13") (pinfunction "CLK_13") (pintype "input"))
      (node (ref "U3") (pin "18") (pinfunction "GND_18") (pintype "passive"))
      (node (ref "U3") (pin "25") (pinfunction "GND_25") (pintype "passive"))
      (node (ref "U3") (pin "29") (pinfunction "P_PAD_29") (pintype "passive"))
      (node (ref "U3") (pin "3") (pinfunction "GND_3") (pintype "passive"))
    )
    (net (code "76") (name "unconnected-(U1-DIAG-Pad11)") (class "Default")
      (node (ref "U1") (pin "11") (pinfunction "DIAG_11") (pintype "output+no_connect"))
    )
    (net (code "77") (name "unconnected-(U1-INDEX-Pad12)") (class "Default")
      (node (ref "U1") (pin "12") (pinfunction "INDEX_12") (pintype "output+no_connect"))
    )
    (net (code "78") (name "unconnected-(U1-PDN_UART-Pad14)") (class "Default")
      (node (ref "U1") (pin "14") (pinfunction "PDN_UART_14") (pintype "bidirectional+no_connect"))
    )
    (net (code "79") (name "unconnected-(U1-STDBY-Pad20)") (class "Default")
      (node (ref "U1") (pin "20") (pinfunction "STDBY_20") (pintype "input+no_connect"))
    )
    (net (code "80") (name "unconnected-(U2-DIAG-Pad11)") (class "Default")
      (node (ref "U2") (pin "11") (pinfunction "DIAG_11") (pintype "output+no_connect"))
    )
    (net (code "81") (name "unconnected-(U2-INDEX-Pad12)") (class "Default")
      (node (ref "U2") (pin "12") (pinfunction "INDEX_12") (pintype "output+no_connect"))
    )
    (net (code "82") (name "unconnected-(U2-PDN_UART-Pad14)") (class "Default")
      (node (ref "U2") (pin "14") (pinfunction "PDN_UART_14") (pintype "bidirectional+no_connect"))
    )
    (net (code "83") (name "unconnected-(U2-STDBY-Pad20)") (class "Default")
      (node (ref "U2") (pin "20") (pinfunction "STDBY_20") (pintype "input+no_connect"))
    )
    (net (code "84") (name "unconnected-(U3-DIAG-Pad11)") (class "Default")
      (node (ref "U3") (pin "11") (pinfunction "DIAG_11") (pintype "output+no_connect"))
    )
    (net (code "85") (name "unconnected-(U3-INDEX-Pad12)") (class "Default")
      (node (ref "U3") (pin "12") (pinfunction "INDEX_12") (pintype "output+no_connect"))
    )
    (net (code "86") (name "unconnected-(U3-PDN_UART-Pad14)") (class "Default")
      (node (ref "U3") (pin "14") (pinfunction "PDN_UART_14") (pintype "bidirectional+no_connect"))
    )
    (net (code "87") (name "unconnected-(U3-STDBY-Pad20)") (class "Default")
      (node (ref "U3") (pin "20") (pinfunction "STDBY_20") (pintype "input+no_connect"))
    )
  )
)
